# Schematics.net
KiCad netlist of a schematic drawn in Altium Designer
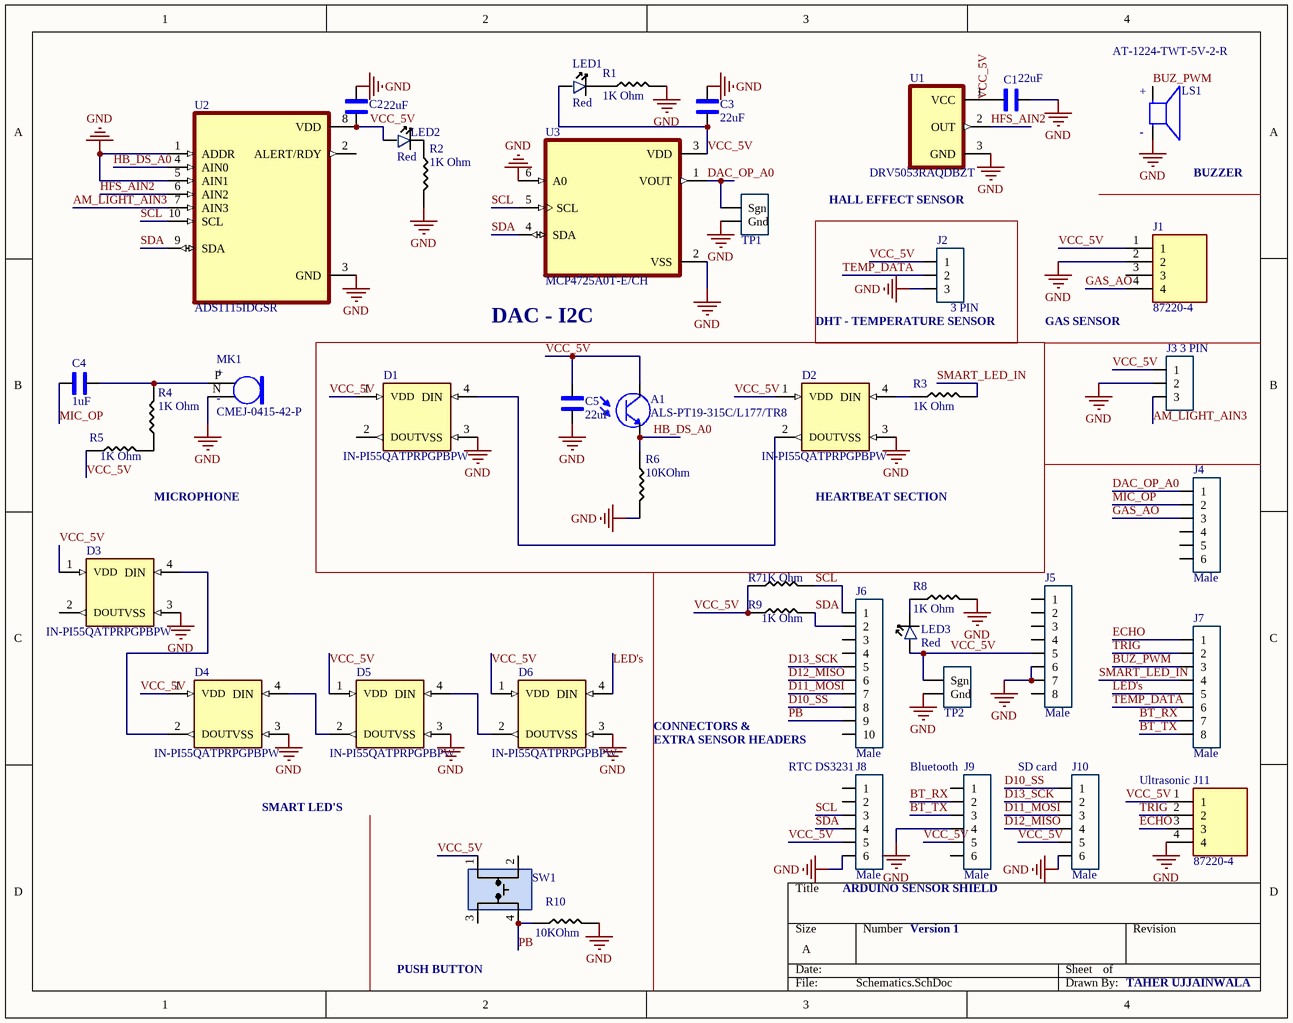
[diagram p0: Schematics.SchDoc]

(export (version "E")
  (design (tool "Eeschema 10.0.6"))
  (components
    (comp (ref "A1")
      (value "ALS-PT19-315C/L177/TR8")
      (footprint "XDCR_ALS-PT19-315C/L177/TR8")
      (description "Phototransistors 630nm 2-SMD, No Lead")
      (fields (field (name "MF") "Everlight"))
      (libsource (lib "ALS-PT19-315C_L177_TR8") (part "ALS-PT19-315C/L177/TR8"))
    )
    (comp (ref "C1")
      (value "22uF")
      (footprint "1206_Passive_Capacitor")
      (description "22µF ±20% 16V Ceramic Capacitor X5R 1206 (3216 Metric)")
      (fields (field (name "DIGIKEY PART") "1276-2728-1-ND") (field (name "MFR PART #") "CL31A226KPHNNNE"))
      (libsource (lib "ECEN5730Lib_Manual_2021_08") (part "C_22uF_1206"))
    )
    (comp (ref "C2")
      (value "22uF")
      (footprint "1206_Passive_Capacitor")
      (description "22µF ±20% 16V Ceramic Capacitor X5R 1206 (3216 Metric)")
      (fields (field (name "DIGIKEY PART") "1276-2728-1-ND") (field (name "MFR PART #") "CL31A226KPHNNNE"))
      (libsource (lib "ECEN5730Lib_Manual_2021_08") (part "C_22uF_1206"))
    )
    (comp (ref "C3")
      (value "22uF")
      (footprint "1206_Passive_Capacitor")
      (description "22µF ±20% 16V Ceramic Capacitor X5R 1206 (3216 Metric)")
      (fields (field (name "DIGIKEY PART") "1276-2728-1-ND") (field (name "MFR PART #") "CL31A226KPHNNNE"))
      (libsource (lib "ECEN5730Lib_Manual_2021_08") (part "C_22uF_1206"))
    )
    (comp (ref "C4")
      (value "1uF")
      (footprint "1206_Passive_Capacitor")
      (description "1µF ±20% 16V Ceramic Capacitor X7R 1206 (3216 Metric)")
      (fields (field (name "DIGIKEY PART") "399-8150-1-ND") (field (name "MFR PART #") "CL31B105KBHNNNE"))
      (libsource (lib "ECEN5730Lib_Manual_2021_08") (part "C_1uF_1206"))
    )
    (comp (ref "C5")
      (value "22uF")
      (footprint "1206_Passive_Capacitor")
      (description "22µF ±20% 16V Ceramic Capacitor X5R 1206 (3216 Metric)")
      (fields (field (name "DIGIKEY PART") "1276-2728-1-ND") (field (name "MFR PART #") "CL31A226KPHNNNE"))
      (libsource (lib "ECEN5730Lib_Manual_2021_08") (part "C_22uF_1206"))
    )
    (comp (ref "D1")
      (value "IN-PI55QATPRPGPBPW")
      (footprint "SERIAL_LED")
      (description "Digital Series Cascade LED")
      (libsource (lib "ECEN5730Lib_Manual_2021_08") (part "LED_Smart_5050"))
    )
    (comp (ref "D2")
      (value "IN-PI55QATPRPGPBPW")
      (footprint "SERIAL_LED")
      (description "Digital Series Cascade LED")
      (libsource (lib "ECEN5730Lib_Manual_2021_08") (part "LED_Smart_5050"))
    )
    (comp (ref "D3")
      (value "IN-PI55QATPRPGPBPW")
      (footprint "SERIAL_LED")
      (description "Digital Series Cascade LED")
      (libsource (lib "ECEN5730Lib_Manual_2021_08") (part "LED_Smart_5050"))
    )
    (comp (ref "D4")
      (value "IN-PI55QATPRPGPBPW")
      (footprint "SERIAL_LED")
      (description "Digital Series Cascade LED")
      (libsource (lib "ECEN5730Lib_Manual_2021_08") (part "LED_Smart_5050"))
    )
    (comp (ref "D5")
      (value "IN-PI55QATPRPGPBPW")
      (footprint "SERIAL_LED")
      (description "Digital Series Cascade LED")
      (libsource (lib "ECEN5730Lib_Manual_2021_08") (part "LED_Smart_5050"))
    )
    (comp (ref "D6")
      (value "IN-PI55QATPRPGPBPW")
      (footprint "SERIAL_LED")
      (description "Digital Series Cascade LED")
      (libsource (lib "ECEN5730Lib_Manual_2021_08") (part "LED_Smart_5050"))
    )
    (comp (ref "J1")
      (value "87220-4")
      (footprint "TE_87220-4")
      (description "Conn Unshrouded Header HDR 4 POS 2.54mm Solder ST Thru-Hole Carton")
      (fields (field (name "MF") "TE Connectivity"))
      (libsource (lib "87220-4") (part "87220-4"))
    )
    (comp (ref "J2")
      (value "3 PIN")
      (footprint "3_PIN_100mil")
      (description "3 2.54mm Straight 1 Header，Breakaway Through Hole Pin Header & Female Header ROHS")
      (fields (field (name "LCSC PART#") "C49257"))
      (libsource (lib "ECEN5730Lib_JLC_2021_08") (part "J_3_PIN_HEADER"))
    )
    (comp (ref "J3")
      (value "3 PIN")
      (footprint "3_PIN_100mil")
      (description "3 2.54mm Straight 1 Header，Breakaway Through Hole Pin Header & Female Header ROHS")
      (fields (field (name "LCSC PART#") "C49257"))
      (libsource (lib "ECEN5730Lib_JLC_2021_08") (part "J_3_PIN_HEADER"))
    )
    (comp (ref "J4")
      (value "Male")
      (footprint "6_PIN_ARDUINO_100mil")
      (description "6 Position Header Connector 0.100\" (2.54mm) Through Hole Tin")
      (fields (field (name "DIGIKEY PART") "S7004-ND") (field (name "LCSC PART#") "DNP"))
      (libsource (lib "ECEN5730Lib_Manual_2021_08") (part "JM_6_PIN_MALE_ARDUINO"))
    )
    (comp (ref "J5")
      (value "Male")
      (footprint "8_PIN_ARDUINO_100MIL")
      (description "8 Position Header Connector 0.100\" (2.54mm) Through Hole Tin")
      (fields (field (name "DIGIKEY PART") "S7006-ND") (field (name "LCSC PART#") "DNP"))
      (libsource (lib "ECEN5730Lib_Manual_2021_08") (part "JM_8_PIN_MALE_ARDUINO"))
    )
    (comp (ref "J6")
      (value "Male")
      (footprint "10_PIN_ARDUINO_100MIL")
      (description "10 Position Header Connector 0.100\" (2.54mm) Through Hole Tin")
      (fields (field (name "DIGIKEY PART") "S7008-ND") (field (name "LCSC PART#") "DNP"))
      (libsource (lib "ECEN5730Lib_Manual_2021_08") (part "JM_10_PIN_MALE_ARDUINO"))
    )
    (comp (ref "J7")
      (value "Male")
      (footprint "8_PIN_ARDUINO_100MIL")
      (description "8 Position Header Connector 0.100\" (2.54mm) Through Hole Tin")
      (fields (field (name "DIGIKEY PART") "S7006-ND") (field (name "LCSC PART#") "DNP"))
      (libsource (lib "ECEN5730Lib_Manual_2021_08") (part "JM_8_PIN_MALE_ARDUINO"))
    )
    (comp (ref "J8")
      (value "Male")
      (footprint "6_PIN_ARDUINO_100mil")
      (description "6 Position Header Connector 0.100\" (2.54mm) Through Hole Tin")
      (fields (field (name "DIGIKEY PART") "S7004-ND") (field (name "LCSC PART#") "DNP"))
      (libsource (lib "ECEN5730Lib_Manual_2021_08") (part "JM_6_PIN_MALE_ARDUINO"))
    )
    (comp (ref "J9")
      (value "Male")
      (footprint "6_PIN_ARDUINO_100mil")
      (description "6 Position Header Connector 0.100\" (2.54mm) Through Hole Tin")
      (fields (field (name "DIGIKEY PART") "S7004-ND") (field (name "LCSC PART#") "DNP"))
      (libsource (lib "ECEN5730Lib_Manual_2021_08") (part "JM_6_PIN_MALE_ARDUINO"))
    )
    (comp (ref "J10")
      (value "Male")
      (footprint "6_PIN_ARDUINO_100mil")
      (description "6 Position Header Connector 0.100\" (2.54mm) Through Hole Tin")
      (fields (field (name "DIGIKEY PART") "S7004-ND") (field (name "LCSC PART#") "DNP"))
      (libsource (lib "ECEN5730Lib_Manual_2021_08") (part "JM_6_PIN_MALE_ARDUINO"))
    )
    (comp (ref "J11")
      (value "87220-4")
      (footprint "TE_87220-4")
      (description "Conn Unshrouded Header HDR 4 POS 2.54mm Solder ST Thru-Hole Carton")
      (fields (field (name "MF") "TE Connectivity"))
      (libsource (lib "87220-4") (part "87220-4"))
    )
    (comp (ref "LED1")
      (value "Red")
      (footprint "LED")
      (description "Red 638nm LED Indication - Discrete 1.8V 1206 (3216 Metric)")
      (fields (field (name "DIGIKEY PART") "160-1167-1-ND") (field (name "Comment") "LTST-C150CKT"))
      (libsource (lib "ECEN5730Lib_Manual_2021_08") (part "LED_1206"))
    )
    (comp (ref "LED2")
      (value "Red")
      (footprint "LED")
      (description "Red 638nm LED Indication - Discrete 1.8V 1206 (3216 Metric)")
      (fields (field (name "DIGIKEY PART") "160-1167-1-ND") (field (name "Comment") "LTST-C150CKT"))
      (libsource (lib "ECEN5730Lib_Manual_2021_08") (part "LED_1206"))
    )
    (comp (ref "LED3")
      (value "Red")
      (footprint "LED")
      (description "Red 638nm LED Indication - Discrete 1.8V 1206 (3216 Metric)")
      (fields (field (name "DIGIKEY PART") "160-1167-1-ND") (field (name "Comment") "LTST-C150CKT"))
      (libsource (lib "ECEN5730Lib_Manual_2021_08") (part "LED_1206"))
    )
    (comp (ref "LS1")
      (value "AT-1224-TWT-5V-2-R")
      (footprint "XDCR_AT-1224-TWT-5V-2-R")
      (description "AUDIO TRANSDUCER 5 VP-P 87 DB 2400 HZ")
      (fields (field (name "MF") "PUI Audio,"))
      (libsource (lib "AT-1224-TWT-5V-2-R") (part "AT-1224-TWT-5V-2-R"))
    )
    (comp (ref "MK1")
      (value "CMEJ-0415-42-P")
      (footprint "MIC_CMEJ-0415-42-P")
      (fields (field (name "MF") "CUI Devices") (field (name "DIGI-KEY_PART_NUMBER") "102-6542-ND"))
      (libsource (lib "CMEJ-0415-42-P") (part "CMEJ-0415-42-P"))
    )
    (comp (ref "R1")
      (value "1K Ohm")
      (footprint "1206_Passive_Resitor")
      (description "1 kOhms ±1% 0.5W, 1/2W Chip Resistor 1206 (3216 Metric) Anti-Sulfur, Moisture Resistant Thin Film")
      (fields
        (field (name "DIGIKEY PART") "RNCP1206FTD1K00CT-ND")
        (field (name "MFR PART #") "1206W4F1001T5")
      )
      (libsource (lib "ECEN5730Lib_Manual_2021_08") (part "R_1K_1206"))
    )
    (comp (ref "R2")
      (value "1K Ohm")
      (footprint "1206_Passive_Resitor")
      (description "1 kOhms ±1% 0.5W, 1/2W Chip Resistor 1206 (3216 Metric) Anti-Sulfur, Moisture Resistant Thin Film")
      (fields
        (field (name "DIGIKEY PART") "RNCP1206FTD1K00CT-ND")
        (field (name "MFR PART #") "1206W4F1001T5")
      )
      (libsource (lib "ECEN5730Lib_Manual_2021_08") (part "R_1K_1206"))
    )
    (comp (ref "R3")
      (value "1K Ohm")
      (footprint "1206_Passive_Resitor")
      (description "1 kOhms ±1% 0.5W, 1/2W Chip Resistor 1206 (3216 Metric) Anti-Sulfur, Moisture Resistant Thin Film")
      (fields
        (field (name "DIGIKEY PART") "RNCP1206FTD1K00CT-ND")
        (field (name "MFR PART #") "1206W4F1001T5")
      )
      (libsource (lib "ECEN5730Lib_Manual_2021_08") (part "R_1K_1206"))
    )
    (comp (ref "R4")
      (value "1K Ohm")
      (footprint "1206_Passive_Resitor")
      (description "1 kOhms ±1% 0.5W, 1/2W Chip Resistor 1206 (3216 Metric) Anti-Sulfur, Moisture Resistant Thin Film")
      (fields
        (field (name "DIGIKEY PART") "RNCP1206FTD1K00CT-ND")
        (field (name "MFR PART #") "1206W4F1001T5")
      )
      (libsource (lib "ECEN5730Lib_Manual_2021_08") (part "R_1K_1206"))
    )
    (comp (ref "R5")
      (value "1K Ohm")
      (footprint "1206_Passive_Resitor")
      (description "1 kOhms ±1% 0.5W, 1/2W Chip Resistor 1206 (3216 Metric) Anti-Sulfur, Moisture Resistant Thin Film")
      (fields
        (field (name "DIGIKEY PART") "RNCP1206FTD1K00CT-ND")
        (field (name "MFR PART #") "1206W4F1001T5")
      )
      (libsource (lib "ECEN5730Lib_Manual_2021_08") (part "R_1K_1206"))
    )
    (comp (ref "R6")
      (value "10KOhm")
      (footprint "1206_Passive_Resitor")
      (description "10 kOhms ±5% 0.25W, 1/4W Chip Resistor 1206 (3216 Metric) Automotive AEC-Q200 Thick Film")
      (fields (field (name "DIGIKEY PART") "RMCF1206JT300RCT-ND") (field (name "Comment") "10k"))
      (libsource (lib "ECEN5730Lib_Manual_2021_08") (part "R_10KOhm_1206"))
    )
    (comp (ref "R7")
      (value "1K Ohm")
      (footprint "1206_Passive_Resitor")
      (description "1 kOhms ±1% 0.5W, 1/2W Chip Resistor 1206 (3216 Metric) Anti-Sulfur, Moisture Resistant Thin Film")
      (fields
        (field (name "DIGIKEY PART") "RNCP1206FTD1K00CT-ND")
        (field (name "MFR PART #") "1206W4F1001T5")
      )
      (libsource (lib "ECEN5730Lib_Manual_2021_08") (part "R_1K_1206"))
    )
    (comp (ref "R8")
      (value "1K Ohm")
      (footprint "1206_Passive_Resitor")
      (description "1 kOhms ±1% 0.5W, 1/2W Chip Resistor 1206 (3216 Metric) Anti-Sulfur, Moisture Resistant Thin Film")
      (fields
        (field (name "DIGIKEY PART") "RNCP1206FTD1K00CT-ND")
        (field (name "MFR PART #") "1206W4F1001T5")
      )
      (libsource (lib "ECEN5730Lib_Manual_2021_08") (part "R_1K_1206"))
    )
    (comp (ref "R9")
      (value "1K Ohm")
      (footprint "1206_Passive_Resitor")
      (description "1 kOhms ±1% 0.5W, 1/2W Chip Resistor 1206 (3216 Metric) Anti-Sulfur, Moisture Resistant Thin Film")
      (fields
        (field (name "DIGIKEY PART") "RNCP1206FTD1K00CT-ND")
        (field (name "MFR PART #") "1206W4F1001T5")
      )
      (libsource (lib "ECEN5730Lib_Manual_2021_08") (part "R_1K_1206"))
    )
    (comp (ref "R10")
      (value "10KOhm")
      (footprint "1206_Passive_Resitor")
      (description "10 kOhms ±5% 0.25W, 1/4W Chip Resistor 1206 (3216 Metric) Automotive AEC-Q200 Thick Film")
      (fields (field (name "DIGIKEY PART") "RMCF1206JT300RCT-ND") (field (name "LCSC PART#") "C17902"))
      (libsource (lib "ECEN5730Lib_JLC_2021_08") (part "R_10KOhm_1206"))
    )
    (comp (ref "SW1")
      (value "TL3305AF160QG")
      (footprint "Switch_JLC")
      (description "Tactile Switch SPST-NO Top Actuated Surface Mount")
      (fields (field (name "MFR PART #") "C174049"))
      (libsource (lib "ECEN5730Lib_JLC_2021_08") (part "SW_Push_Button_JLC"))
    )
    (comp (ref "TP1")
      (value "10x Probe TP")
      (footprint "TP10x_Probe")
      (description "Test Point 300 mil centers")
      (libsource (lib "ECEN5730Lib_Manual_2021_08") (part "TP_10x_Probe"))
    )
    (comp (ref "TP2")
      (value "10x Probe TP")
      (footprint "TP10x_Probe")
      (description "Test Point 300 mil centers")
      (libsource (lib "ECEN5730Lib_Manual_2021_08") (part "TP_10x_Probe"))
    )
    (comp (ref "U1")
      (value "DRV5053RAQDBZT")
      (footprint "SOT95P237X112-3N")
      (description "SENSOR LINEAR ANALOG SOT23-3")
      (libsource (lib "DRV5053RAQDBZT") (part "DRV5053RAQDBZT"))
    )
    (comp (ref "U2")
      (value "ADS1115IDGSR")
      (footprint "SOP50P490X110-10N")
      (fields (field (name "MF") "Texas Instruments"))
      (libsource (lib "ADS1115IDGSR") (part "ADS1115IDGSR"))
    )
    (comp (ref "U3")
      (value "MCP4725A0T-E/CH")
      (footprint "SOT95P270X145-6N")
      (description "12 Bit Digital to Analog Converter 1 SOT-23-6")
      (fields (field (name "MF") "Microchip"))
      (libsource (lib "MCP4725A0T-E_CH") (part "MCP4725A0T-E/CH"))
    )
  )
  (nets
    (net (code "1") (name "/AM_LIGHT_AIN3") (class "Default")
      (node (ref "J3") (pin "3") (pinfunction "3_3") (pintype "passive"))
      (node (ref "U2") (pin "7") (pinfunction "AIN3_7") (pintype "input"))
    )
    (net (code "2") (name "/BT_RX") (class "Default")
      (node (ref "J7") (pin "7") (pinfunction "7_7") (pintype "passive"))
      (node (ref "J9") (pin "2") (pinfunction "2_2") (pintype "passive"))
    )
    (net (code "3") (name "/BT_TX") (class "Default")
      (node (ref "J7") (pin "8") (pinfunction "8_8") (pintype "passive"))
      (node (ref "J9") (pin "3") (pinfunction "3_3") (pintype "passive"))
    )
    (net (code "4") (name "/BUZ_PWM") (class "Default")
      (node (ref "J7") (pin "3") (pinfunction "3_3") (pintype "passive"))
      (node (ref "LS1") (pin "P") (pinfunction "P_P") (pintype "passive"))
    )
    (net (code "5") (name "/D10_SS") (class "Default")
      (node (ref "J10") (pin "1") (pinfunction "1_1") (pintype "passive"))
      (node (ref "J6") (pin "8") (pinfunction "8_8") (pintype "passive"))
    )
    (net (code "6") (name "/D11_MOSI") (class "Default")
      (node (ref "J10") (pin "3") (pinfunction "3_3") (pintype "passive"))
      (node (ref "J6") (pin "7") (pinfunction "7_7") (pintype "passive"))
    )
    (net (code "7") (name "/D12_MISO") (class "Default")
      (node (ref "J10") (pin "4") (pinfunction "4_4") (pintype "passive"))
      (node (ref "J6") (pin "6") (pinfunction "6_6") (pintype "passive"))
    )
    (net (code "8") (name "/D13_SCK") (class "Default")
      (node (ref "J10") (pin "2") (pinfunction "2_2") (pintype "passive"))
      (node (ref "J6") (pin "5") (pinfunction "5_5") (pintype "passive"))
    )
    (net (code "9") (name "/DAC_OP_A0") (class "Default")
      (node (ref "J4") (pin "1") (pinfunction "1_1") (pintype "passive"))
      (node (ref "TP1") (pin "1") (pinfunction "Sgn_1") (pintype "passive"))
      (node (ref "U3") (pin "1") (pinfunction "VOUT_1") (pintype "output"))
    )
    (net (code "10") (name "/ECHO") (class "Default")
      (node (ref "J11") (pin "3") (pinfunction "3_3") (pintype "passive"))
      (node (ref "J7") (pin "1") (pinfunction "1_1") (pintype "passive"))
    )
    (net (code "11") (name "/GAS_AO") (class "Default")
      (node (ref "J1") (pin "4") (pinfunction "4_4") (pintype "passive"))
      (node (ref "J4") (pin "3") (pinfunction "3_3") (pintype "passive"))
    )
    (net (code "12") (name "/HB_DS_A0") (class "Default")
      (node (ref "A1") (pin "2") (pinfunction "E_2") (pintype "passive"))
      (node (ref "R6") (pin "1") (pinfunction "1_1") (pintype "passive"))
      (node (ref "U2") (pin "4") (pinfunction "AIN0_4") (pintype "input"))
    )
    (net (code "13") (name "/HFS_AIN2") (class "Default")
      (node (ref "U1") (pin "2") (pinfunction "OUT_2") (pintype "output"))
      (node (ref "U2") (pin "6") (pinfunction "AIN2_6") (pintype "input"))
    )
    (net (code "14") (name "/LED's") (class "Default")
      (node (ref "D6") (pin "4") (pinfunction "DIN_4") (pintype "input"))
      (node (ref "J7") (pin "5") (pinfunction "5_5") (pintype "passive"))
    )
    (net (code "15") (name "/MIC_OP") (class "Default")
      (node (ref "C4") (pin "1") (pinfunction "1_1") (pintype "passive"))
      (node (ref "J4") (pin "2") (pinfunction "2_2") (pintype "passive"))
    )
    (net (code "16") (name "/PB") (class "Default")
      (node (ref "J6") (pin "9") (pinfunction "9_9") (pintype "passive"))
      (node (ref "R10") (pin "1") (pinfunction "1_1") (pintype "passive"))
      (node (ref "SW1") (pin "4") (pinfunction "4_4") (pintype "passive"))
    )
    (net (code "17") (name "/SCL") (class "Default")
      (node (ref "J6") (pin "1") (pinfunction "1_1") (pintype "passive"))
      (node (ref "J8") (pin "3") (pinfunction "3_3") (pintype "passive"))
      (node (ref "R7") (pin "2") (pinfunction "2_2") (pintype "passive"))
      (node (ref "U2") (pin "10") (pinfunction "SCL_10") (pintype "input"))
      (node (ref "U3") (pin "5") (pinfunction "SCL_5") (pintype "input"))
    )
    (net (code "18") (name "/SDA") (class "Default")
      (node (ref "J6") (pin "2") (pinfunction "2_2") (pintype "passive"))
      (node (ref "J8") (pin "4") (pinfunction "4_4") (pintype "passive"))
      (node (ref "R9") (pin "2") (pinfunction "2_2") (pintype "passive"))
      (node (ref "U2") (pin "9") (pinfunction "SDA_9") (pintype "bidirectional"))
      (node (ref "U3") (pin "4") (pinfunction "SDA_4") (pintype "bidirectional"))
    )
    (net (code "19") (name "/SMART_LED_IN") (class "Default")
      (node (ref "J7") (pin "4") (pinfunction "4_4") (pintype "passive"))
      (node (ref "R3") (pin "2") (pinfunction "2_2") (pintype "passive"))
    )
    (net (code "20") (name "/TEMP_DATA") (class "Default")
      (node (ref "J2") (pin "2") (pinfunction "2_2") (pintype "passive"))
      (node (ref "J7") (pin "6") (pinfunction "6_6") (pintype "passive"))
    )
    (net (code "21") (name "/TRIG") (class "Default")
      (node (ref "J11") (pin "2") (pinfunction "2_2") (pintype "passive"))
      (node (ref "J7") (pin "2") (pinfunction "2_2") (pintype "passive"))
    )
    (net (code "22") (name "/VCC_5V") (class "Default")
      (node (ref "A1") (pin "1") (pinfunction "C_1") (pintype "passive"))
      (node (ref "C1") (pin "1") (pinfunction "1_1") (pintype "passive"))
      (node (ref "C2") (pin "1") (pinfunction "1_1") (pintype "passive"))
      (node (ref "C3") (pin "1") (pinfunction "1_1") (pintype "passive"))
      (node (ref "C5") (pin "2") (pinfunction "2_2") (pintype "passive"))
      (node (ref "D1") (pin "1") (pinfunction "VDD_1") (pintype "input"))
      (node (ref "D2") (pin "1") (pinfunction "VDD_1") (pintype "input"))
      (node (ref "D3") (pin "1") (pinfunction "VDD_1") (pintype "input"))
      (node (ref "D4") (pin "1") (pinfunction "VDD_1") (pintype "input"))
      (node (ref "D5") (pin "1") (pinfunction "VDD_1") (pintype "input"))
      (node (ref "D6") (pin "1") (pinfunction "VDD_1") (pintype "input"))
      (node (ref "J1") (pin "1") (pinfunction "1_1") (pintype "passive"))
      (node (ref "J10") (pin "5") (pinfunction "5_5") (pintype "passive"))
      (node (ref "J11") (pin "1") (pinfunction "1_1") (pintype "passive"))
      (node (ref "J2") (pin "1") (pinfunction "1_1") (pintype "passive"))
      (node (ref "J3") (pin "1") (pinfunction "1_1") (pintype "passive"))
      (node (ref "J5") (pin "5") (pinfunction "5_5") (pintype "passive"))
      (node (ref "J8") (pin "5") (pinfunction "5_5") (pintype "passive"))
      (node (ref "J9") (pin "5") (pinfunction "5_5") (pintype "passive"))
      (node (ref "LED1") (pin "2") (pinfunction "2_2") (pintype "passive"))
      (node (ref "LED2") (pin "2") (pinfunction "2_2") (pintype "passive"))
      (node (ref "LED3") (pin "2") (pinfunction "2_2") (pintype "passive"))
      (node (ref "R5") (pin "1") (pinfunction "1_1") (pintype "passive"))
      (node (ref "R7") (pin "1") (pinfunction "1_1") (pintype "passive"))
      (node (ref "R9") (pin "1") (pinfunction "1_1") (pintype "passive"))
      (node (ref "SW1") (pin "1") (pinfunction "1_1") (pintype "passive"))
      (node (ref "TP2") (pin "1") (pinfunction "Sgn_1") (pintype "passive"))
      (node (ref "U1") (pin "1") (pinfunction "VCC_1") (pintype "power_in"))
      (node (ref "U2") (pin "8") (pinfunction "VDD_8") (pintype "power_in"))
      (node (ref "U3") (pin "3") (pinfunction "VDD_3") (pintype "power_in"))
    )
    (net (code "23") (name "GND") (class "Default")
      (node (ref "C1") (pin "2") (pinfunction "2_2") (pintype "passive"))
      (node (ref "C2") (pin "2") (pinfunction "2_2") (pintype "passive"))
      (node (ref "C3") (pin "2") (pinfunction "2_2") (pintype "passive"))
      (node (ref "C5") (pin "1") (pinfunction "1_1") (pintype "passive"))
      (node (ref "D1") (pin "3") (pinfunction "VSS_3") (pintype "input"))
      (node (ref "D2") (pin "3") (pinfunction "VSS_3") (pintype "input"))
      (node (ref "D3") (pin "3") (pinfunction "VSS_3") (pintype "input"))
      (node (ref "D4") (pin "3") (pinfunction "VSS_3") (pintype "input"))
      (node (ref "D5") (pin "3") (pinfunction "VSS_3") (pintype "input"))
      (node (ref "D6") (pin "3") (pinfunction "VSS_3") (pintype "input"))
      (node (ref "J1") (pin "2") (pinfunction "2_2") (pintype "passive"))
      (node (ref "J10") (pin "6") (pinfunction "6_6") (pintype "passive"))
      (node (ref "J11") (pin "4") (pinfunction "4_4") (pintype "passive"))
      (node (ref "J2") (pin "3") (pinfunction "3_3") (pintype "passive"))
      (node (ref "J3") (pin "2") (pinfunction "2_2") (pintype "passive"))
      (node (ref "J5") (pin "6") (pinfunction "6_6") (pintype "passive"))
      (node (ref "J5") (pin "7") (pinfunction "7_7") (pintype "passive"))
      (node (ref "J8") (pin "6") (pinfunction "6_6") (pintype "passive"))
      (node (ref "J9") (pin "4") (pinfunction "4_4") (pintype "passive"))
      (node (ref "LS1") (pin "N") (pinfunction "N_N") (pintype "passive"))
      (node (ref "MK1") (pin "N") (pinfunction "GND_N") (pintype "passive"))
      (node (ref "R1") (pin "2") (pinfunction "2_2") (pintype "passive"))
      (node (ref "R10") (pin "2") (pinfunction "2_2") (pintype "passive"))
      (node (ref "R2") (pin "2") (pinfunction "2_2") (pintype "passive"))
      (node (ref "R6") (pin "2") (pinfunction "2_2") (pintype "passive"))
      (node (ref "R8") (pin "2") (pinfunction "2_2") (pintype "passive"))
      (node (ref "TP1") (pin "2") (pinfunction "Gnd_2") (pintype "passive"))
      (node (ref "TP2") (pin "2") (pinfunction "Gnd_2") (pintype "passive"))
      (node (ref "U1") (pin "3") (pinfunction "GND_3") (pintype "power_in"))
      (node (ref "U2") (pin "1") (pinfunction "ADDR_1") (pintype "input"))
      (node (ref "U2") (pin "3") (pinfunction "GND_3") (pintype "power_in"))
      (node (ref "U2") (pin "5") (pinfunction "AIN1_5") (pintype "input"))
      (node (ref "U3") (pin "2") (pinfunction "VSS_2") (pintype "power_in"))
      (node (ref "U3") (pin "6") (pinfunction "A0_6") (pintype "input"))
    )
    (net (code "24") (name "Net-(D1-DIN)") (class "Default")
      (node (ref "D1") (pin "4") (pinfunction "DIN_4") (pintype "input"))
      (node (ref "D2") (pin "2") (pinfunction "DOUT_2") (pintype "output"))
    )
    (net (code "25") (name "Net-(D2-DIN)") (class "Default")
      (node (ref "D2") (pin "4") (pinfunction "DIN_4") (pintype "input"))
      (node (ref "R3") (pin "1") (pinfunction "1_1") (pintype "passive"))
    )
    (net (code "26") (name "Net-(D3-DIN)") (class "Default")
      (node (ref "D3") (pin "4") (pinfunction "DIN_4") (pintype "input"))
      (node (ref "D4") (pin "2") (pinfunction "DOUT_2") (pintype "output"))
    )
    (net (code "27") (name "Net-(D4-DIN)") (class "Default")
      (node (ref "D4") (pin "4") (pinfunction "DIN_4") (pintype "input"))
      (node (ref "D5") (pin "2") (pinfunction "DOUT_2") (pintype "output"))
    )
    (net (code "28") (name "Net-(D5-DIN)") (class "Default")
      (node (ref "D5") (pin "4") (pinfunction "DIN_4") (pintype "input"))
      (node (ref "D6") (pin "2") (pinfunction "DOUT_2") (pintype "output"))
    )
    (net (code "29") (name "Net-(LED1-Pad1)") (class "Default")
      (node (ref "LED1") (pin "1") (pinfunction "1_1") (pintype "passive"))
      (node (ref "R1") (pin "1") (pinfunction "1_1") (pintype "passive"))
    )
    (net (code "30") (name "Net-(LED2-Pad1)") (class "Default")
      (node (ref "LED2") (pin "1") (pinfunction "1_1") (pintype "passive"))
      (node (ref "R2") (pin "1") (pinfunction "1_1") (pintype "passive"))
    )
    (net (code "31") (name "Net-(LED3-Pad1)") (class "Default")
      (node (ref "LED3") (pin "1") (pinfunction "1_1") (pintype "passive"))
      (node (ref "R8") (pin "1") (pinfunction "1_1") (pintype "passive"))
    )
    (net (code "32") (name "Net-(MK1-OUTPUT)") (class "Default")
      (node (ref "C4") (pin "2") (pinfunction "2_2") (pintype "passive"))
      (node (ref "MK1") (pin "P") (pinfunction "OUTPUT_P") (pintype "passive"))
      (node (ref "R4") (pin "2") (pinfunction "2_2") (pintype "passive"))
    )
    (net (code "33") (name "Net-(R4-Pad1)") (class "Default")
      (node (ref "R4") (pin "1") (pinfunction "1_1") (pintype "passive"))
      (node (ref "R5") (pin "2") (pinfunction "2_2") (pintype "passive"))
    )
    (net (code "34") (name "unconnected-(D1-DOUT-Pad2)") (class "Default")
      (node (ref "D1") (pin "2") (pinfunction "DOUT_2") (pintype "output"))
    )
    (net (code "35") (name "unconnected-(D3-DOUT-Pad2)") (class "Default")
      (node (ref "D3") (pin "2") (pinfunction "DOUT_2") (pintype "output"))
    )
    (net (code "36") (name "unconnected-(J1-Pad3)") (class "Default")
      (node (ref "J1") (pin "3") (pinfunction "3_3") (pintype "passive"))
    )
    (net (code "37") (name "unconnected-(J4-Pad4)") (class "Default")
      (node (ref "J4") (pin "4") (pinfunction "4_4") (pintype "passive"))
    )
    (net (code "38") (name "unconnected-(J4-Pad5)") (class "Default")
      (node (ref "J4") (pin "5") (pinfunction "5_5") (pintype "passive"))
    )
    (net (code "39") (name "unconnected-(J4-Pad6)") (class "Default")
      (node (ref "J4") (pin "6") (pinfunction "6_6") (pintype "passive"))
    )
    (net (code "40") (name "unconnected-(J5-Pad1)") (class "Default")
      (node (ref "J5") (pin "1") (pinfunction "1_1") (pintype "passive"))
    )
    (net (code "41") (name "unconnected-(J5-Pad2)") (class "Default")
      (node (ref "J5") (pin "2") (pinfunction "2_2") (pintype "passive"))
    )
    (net (code "42") (name "unconnected-(J5-Pad3)") (class "Default")
      (node (ref "J5") (pin "3") (pinfunction "3_3") (pintype "passive"))
    )
    (net (code "43") (name "unconnected-(J5-Pad4)") (class "Default")
      (node (ref "J5") (pin "4") (pinfunction "4_4") (pintype "passive"))
    )
    (net (code "44") (name "unconnected-(J5-Pad8)") (class "Default")
      (node (ref "J5") (pin "8") (pinfunction "8_8") (pintype "passive"))
    )
    (net (code "45") (name "unconnected-(J6-Pad3)") (class "Default")
      (node (ref "J6") (pin "3") (pinfunction "3_3") (pintype "passive"))
    )
    (net (code "46") (name "unconnected-(J6-Pad4)") (class "Default")
      (node (ref "J6") (pin "4") (pinfunction "4_4") (pintype "passive"))
    )
    (net (code "47") (name "unconnected-(J6-Pad10)") (class "Default")
      (node (ref "J6") (pin "10") (pinfunction "10_10") (pintype "passive"))
    )
    (net (code "48") (name "unconnected-(J8-Pad1)") (class "Default")
      (node (ref "J8") (pin "1") (pinfunction "1_1") (pintype "passive"))
    )
    (net (code "49") (name "unconnected-(J8-Pad2)") (class "Default")
      (node (ref "J8") (pin "2") (pinfunction "2_2") (pintype "passive"))
    )
    (net (code "50") (name "unconnected-(J9-Pad1)") (class "Default")
      (node (ref "J9") (pin "1") (pinfunction "1_1") (pintype "passive"))
    )
    (net (code "51") (name "unconnected-(J9-Pad6)") (class "Default")
      (node (ref "J9") (pin "6") (pinfunction "6_6") (pintype "passive"))
    )
    (net (code "52") (name "unconnected-(SW1-Pad2)") (class "Default")
      (node (ref "SW1") (pin "2") (pinfunction "2_2") (pintype "passive"))
    )
    (net (code "53") (name "unconnected-(SW1-Pad3)") (class "Default")
      (node (ref "SW1") (pin "3") (pinfunction "3_3") (pintype "passive"))
    )
    (net (code "54") (name "unconnected-(U2-ALERT{slash}RDY-Pad2)") (class "Default")
      (node (ref "U2") (pin "2") (pinfunction "ALERT/RDY_2") (pintype "output"))
    )
  )
)
